# trill-hex.net
KiCad netlist of a schematic drawn in EAGLE
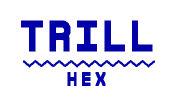
[diagram p0: schematic, sheet 1, part 1 of 2]
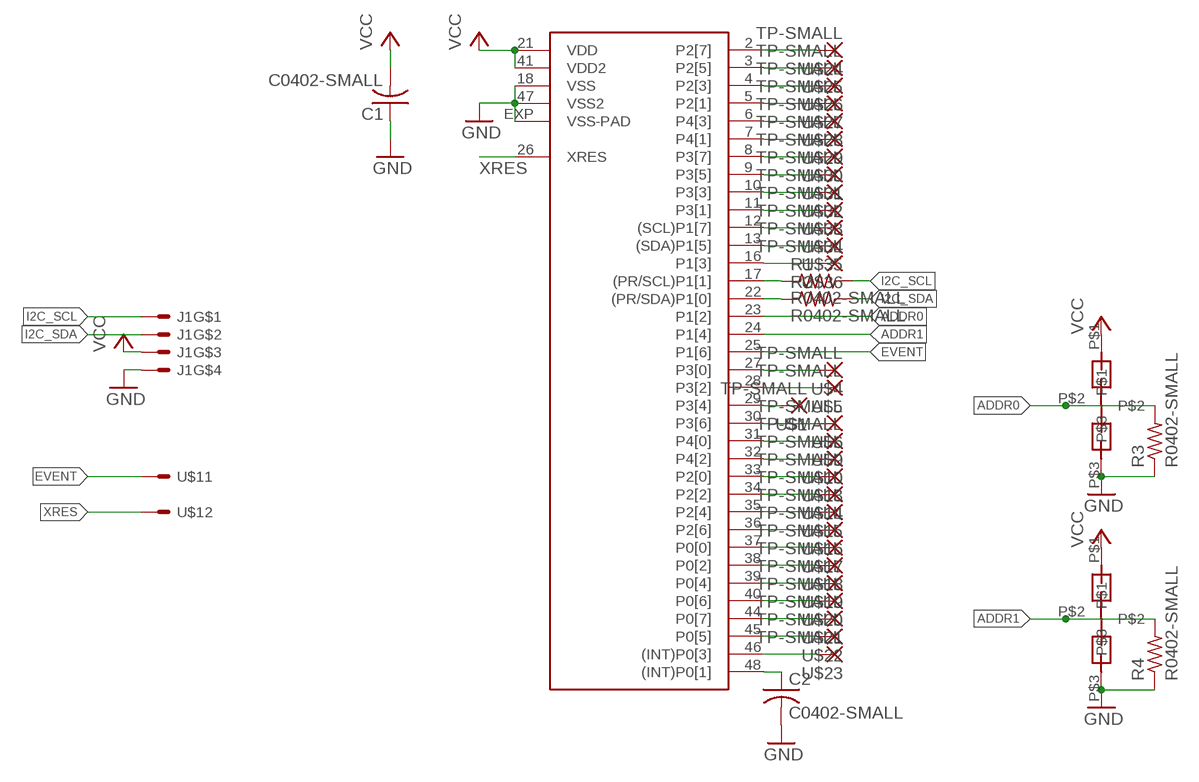
[diagram p1: schematic, sheet 1, part 2 of 2]

(export (version "E")
  (design (tool "Eeschema 10.0.6"))
  (components
    (comp (ref "C1")
      (value "C0402-SMALL")
      (footprint "eagle-import:C0402-SMALL")
      (libsource (lib "eagle-import") (part "C0402-SMALL"))
    )
    (comp (ref "C2")
      (value "C0402-SMALL")
      (footprint "eagle-import:C0402-SMALL")
      (libsource (lib "eagle-import") (part "C0402-SMALL"))
    )
    (comp (ref "IC1")
      (value "CY8C206X6A")
      (footprint "eagle-import:QFN48-LEADS")
      (libsource (lib "eagle-import") (part "CY8C206X6A"))
    )
    (comp (ref "J1")
      (value "GROVE-SMT")
      (footprint "eagle-import:JST-PH-4-SMT")
      (libsource (lib "eagle-import") (part "GROVE-SMT"))
    )
    (comp (ref "R1")
      (value "R0402-SMALL")
      (footprint "eagle-import:C0402-SMALL")
      (libsource (lib "eagle-import") (part "R0402-SMALL"))
    )
    (comp (ref "R2")
      (value "R0402-SMALL")
      (footprint "eagle-import:C0402-SMALL")
      (libsource (lib "eagle-import") (part "R0402-SMALL"))
    )
    (comp (ref "R3")
      (value "R0402-SMALL")
      (footprint "eagle-import:C0402-SMALL")
      (libsource (lib "eagle-import") (part "R0402-SMALL"))
    )
    (comp (ref "R4")
      (value "R0402-SMALL")
      (footprint "eagle-import:C0402-SMALL")
      (libsource (lib "eagle-import") (part "R0402-SMALL"))
    )
    (comp (ref "U$1")
      (value "TP-SMALL")
      (footprint "eagle-import:TESTPAD-SMALL")
      (libsource (lib "eagle-import") (part "TP-SMALL"))
    )
    (comp (ref "U$4")
      (value "TP-SMALL")
      (footprint "eagle-import:TESTPAD-SMALL")
      (libsource (lib "eagle-import") (part "TP-SMALL"))
    )
    (comp (ref "U$5")
      (value "TP-SMALL")
      (footprint "eagle-import:TESTPAD-SMALL")
      (libsource (lib "eagle-import") (part "TP-SMALL"))
    )
    (comp (ref "U$6")
      (value "TP-SMALL")
      (footprint "eagle-import:TESTPAD-SMALL")
      (libsource (lib "eagle-import") (part "TP-SMALL"))
    )
    (comp (ref "U$7")
      (value "SOLDER_JUMPER_3PAD")
      (footprint "eagle-import:SOLDER_JUMPER_3PAD")
      (libsource (lib "eagle-import") (part "SOLDER_JUMPER_3PAD"))
    )
    (comp (ref "U$8")
      (value "SOLDER_JUMPER_3PAD")
      (footprint "eagle-import:SOLDER_JUMPER_3PAD")
      (libsource (lib "eagle-import") (part "SOLDER_JUMPER_3PAD"))
    )
    (comp (ref "U$9")
      (value "TP-SMALL")
      (footprint "eagle-import:TESTPAD-SMALL")
      (libsource (lib "eagle-import") (part "TP-SMALL"))
    )
    (comp (ref "U$10")
      (value "TP-SMALL")
      (footprint "eagle-import:TESTPAD-SMALL")
      (libsource (lib "eagle-import") (part "TP-SMALL"))
    )
    (comp (ref "U$11")
      (value "JST-SMT-EXTRAPAD")
      (footprint "eagle-import:JST-SMT-EXTRAPAD")
      (libsource (lib "eagle-import") (part "JST-SMT-EXTRAPAD"))
    )
    (comp (ref "U$12")
      (value "JST-SMT-EXTRAPAD")
      (footprint "eagle-import:JST-SMT-EXTRAPAD")
      (libsource (lib "eagle-import") (part "JST-SMT-EXTRAPAD"))
    )
    (comp (ref "U$13")
      (value "TP-SMALL")
      (footprint "eagle-import:TESTPAD-SMALL")
      (libsource (lib "eagle-import") (part "TP-SMALL"))
    )
    (comp (ref "U$14")
      (value "TP-SMALL")
      (footprint "eagle-import:TESTPAD-SMALL")
      (libsource (lib "eagle-import") (part "TP-SMALL"))
    )
    (comp (ref "U$15")
      (value "TP-SMALL")
      (footprint "eagle-import:TESTPAD-SMALL")
      (libsource (lib "eagle-import") (part "TP-SMALL"))
    )
    (comp (ref "U$16")
      (value "TP-SMALL")
      (footprint "eagle-import:TESTPAD-SMALL")
      (libsource (lib "eagle-import") (part "TP-SMALL"))
    )
    (comp (ref "U$17")
      (value "TP-SMALL")
      (footprint "eagle-import:TESTPAD-SMALL")
      (libsource (lib "eagle-import") (part "TP-SMALL"))
    )
    (comp (ref "U$18")
      (value "TP-SMALL")
      (footprint "eagle-import:TESTPAD-SMALL")
      (libsource (lib "eagle-import") (part "TP-SMALL"))
    )
    (comp (ref "U$19")
      (value "TP-SMALL")
      (footprint "eagle-import:TESTPAD-SMALL")
      (libsource (lib "eagle-import") (part "TP-SMALL"))
    )
    (comp (ref "U$20")
      (value "TP-SMALL")
      (footprint "eagle-import:TESTPAD-SMALL")
      (libsource (lib "eagle-import") (part "TP-SMALL"))
    )
    (comp (ref "U$21")
      (value "TP-SMALL")
      (footprint "eagle-import:TESTPAD-SMALL")
      (libsource (lib "eagle-import") (part "TP-SMALL"))
    )
    (comp (ref "U$22")
      (value "TP-SMALL")
      (footprint "eagle-import:TESTPAD-SMALL")
      (libsource (lib "eagle-import") (part "TP-SMALL"))
    )
    (comp (ref "U$23")
      (value "TP-SMALL")
      (footprint "eagle-import:TESTPAD-SMALL")
      (libsource (lib "eagle-import") (part "TP-SMALL"))
    )
    (comp (ref "U$24")
      (value "TP-SMALL")
      (footprint "eagle-import:TESTPAD-SMALL")
      (libsource (lib "eagle-import") (part "TP-SMALL"))
    )
    (comp (ref "U$25")
      (value "TP-SMALL")
      (footprint "eagle-import:TESTPAD-SMALL")
      (libsource (lib "eagle-import") (part "TP-SMALL"))
    )
    (comp (ref "U$26")
      (value "TP-SMALL")
      (footprint "eagle-import:TESTPAD-SMALL")
      (libsource (lib "eagle-import") (part "TP-SMALL"))
    )
    (comp (ref "U$27")
      (value "TP-SMALL")
      (footprint "eagle-import:TESTPAD-SMALL")
      (libsource (lib "eagle-import") (part "TP-SMALL"))
    )
    (comp (ref "U$28")
      (value "TP-SMALL")
      (footprint "eagle-import:TESTPAD-SMALL")
      (libsource (lib "eagle-import") (part "TP-SMALL"))
    )
    (comp (ref "U$29")
      (value "TP-SMALL")
      (footprint "eagle-import:TESTPAD-SMALL")
      (libsource (lib "eagle-import") (part "TP-SMALL"))
    )
    (comp (ref "U$30")
      (value "TP-SMALL")
      (footprint "eagle-import:TESTPAD-SMALL")
      (libsource (lib "eagle-import") (part "TP-SMALL"))
    )
    (comp (ref "U$31")
      (value "TP-SMALL")
      (footprint "eagle-import:TESTPAD-SMALL")
      (libsource (lib "eagle-import") (part "TP-SMALL"))
    )
    (comp (ref "U$32")
      (value "TP-SMALL")
      (footprint "eagle-import:TESTPAD-SMALL")
      (libsource (lib "eagle-import") (part "TP-SMALL"))
    )
    (comp (ref "U$33")
      (value "TP-SMALL")
      (footprint "eagle-import:TESTPAD-SMALL")
      (libsource (lib "eagle-import") (part "TP-SMALL"))
    )
    (comp (ref "U$34")
      (value "TP-SMALL")
      (footprint "eagle-import:TESTPAD-SMALL")
      (libsource (lib "eagle-import") (part "TP-SMALL"))
    )
    (comp (ref "U$35")
      (value "TP-SMALL")
      (footprint "eagle-import:TESTPAD-SMALL")
      (libsource (lib "eagle-import") (part "TP-SMALL"))
    )
    (comp (ref "U$36")
      (value "TP-SMALL")
      (footprint "eagle-import:TESTPAD-SMALL")
      (libsource (lib "eagle-import") (part "TP-SMALL"))
    )
  )
  (nets
    (net (code "1") (name "ADDR0") (class "Default")
      (node (ref "IC1") (pin "23") (pinfunction "P1[2]_23") (pintype "bidirectional"))
      (node (ref "R3") (pin "P$2") (pinfunction "2_P$2") (pintype "passive"))
      (node (ref "U$7") (pin "P$2") (pinfunction "P$2_P$2") (pintype "bidirectional"))
    )
    (net (code "2") (name "ADDR1") (class "Default")
      (node (ref "IC1") (pin "24") (pinfunction "P1[4]_24") (pintype "bidirectional"))
      (node (ref "R4") (pin "P$2") (pinfunction "2_P$2") (pintype "passive"))
      (node (ref "U$8") (pin "P$2") (pinfunction "P$2_P$2") (pintype "bidirectional"))
    )
    (net (code "3") (name "EVENT") (class "Default")
      (node (ref "IC1") (pin "25") (pinfunction "P1[6]_25") (pintype "bidirectional"))
      (node (ref "U$11") (pin "P$1") (pinfunction "S_P$1") (pintype "passive"))
    )
    (net (code "4") (name "GND") (class "Default")
      (node (ref "C1") (pin "P$1") (pinfunction "1_P$1") (pintype "passive"))
      (node (ref "C2") (pin "P$2") (pinfunction "2_P$2") (pintype "passive"))
      (node (ref "IC1") (pin "18") (pinfunction "VSS_18") (pintype "bidirectional"))
      (node (ref "IC1") (pin "47") (pinfunction "VSS2_47") (pintype "bidirectional"))
      (node (ref "IC1") (pin "EXP") (pinfunction "VSS-PAD_EXP") (pintype "bidirectional"))
      (node (ref "J1") (pin "4") (pinfunction "S_4") (pintype "passive"))
      (node (ref "R3") (pin "P$1") (pinfunction "1_P$1") (pintype "passive"))
      (node (ref "R4") (pin "P$1") (pinfunction "1_P$1") (pintype "passive"))
      (node (ref "U$7") (pin "P$3") (pinfunction "P$3_P$3") (pintype "bidirectional"))
      (node (ref "U$8") (pin "P$3") (pinfunction "P$3_P$3") (pintype "bidirectional"))
    )
    (net (code "5") (name "I2C_SCL") (class "Default")
      (node (ref "J1") (pin "1") (pinfunction "S_1") (pintype "passive"))
      (node (ref "R1") (pin "P$2") (pinfunction "2_P$2") (pintype "passive"))
    )
    (net (code "6") (name "I2C_SDA") (class "Default")
      (node (ref "J1") (pin "2") (pinfunction "S_2") (pintype "passive"))
      (node (ref "R2") (pin "P$2") (pinfunction "2_P$2") (pintype "passive"))
    )
    (net (code "7") (name "Net-(C2-1)") (class "Default")
      (node (ref "C2") (pin "P$1") (pinfunction "1_P$1") (pintype "passive"))
      (node (ref "IC1") (pin "48") (pinfunction "(INT)P0[1]_48") (pintype "bidirectional"))
    )
    (net (code "8") (name "Net-(IC1-(INT)P0[3])") (class "Default")
      (node (ref "IC1") (pin "46") (pinfunction "(INT)P0[3]_46") (pintype "bidirectional"))
      (node (ref "U$23") (pin "P$1") (pinfunction "P_P$1") (pintype "passive"))
    )
    (net (code "9") (name "Net-(IC1-(PR{slash}SCL)P1[1])") (class "Default")
      (node (ref "IC1") (pin "17") (pinfunction "(PR/SCL)P1[1]_17") (pintype "bidirectional"))
      (node (ref "R1") (pin "P$1") (pinfunction "1_P$1") (pintype "passive"))
    )
    (net (code "10") (name "Net-(IC1-(PR{slash}SDA)P1[0])") (class "Default")
      (node (ref "IC1") (pin "22") (pinfunction "(PR/SDA)P1[0]_22") (pintype "bidirectional"))
      (node (ref "R2") (pin "P$1") (pinfunction "1_P$1") (pintype "passive"))
    )
    (net (code "11") (name "Net-(IC1-(SCL)P1[7])") (class "Default")
      (node (ref "IC1") (pin "12") (pinfunction "(SCL)P1[7]_12") (pintype "bidirectional"))
      (node (ref "U$34") (pin "P$1") (pinfunction "P_P$1") (pintype "passive"))
    )
    (net (code "12") (name "Net-(IC1-(SDA)P1[5])") (class "Default")
      (node (ref "IC1") (pin "13") (pinfunction "(SDA)P1[5]_13") (pintype "bidirectional"))
      (node (ref "U$35") (pin "P$1") (pinfunction "P_P$1") (pintype "passive"))
    )
    (net (code "13") (name "Net-(IC1-P0[0])") (class "Default")
      (node (ref "IC1") (pin "37") (pinfunction "P0[0]_37") (pintype "bidirectional"))
      (node (ref "U$17") (pin "P$1") (pinfunction "P_P$1") (pintype "passive"))
    )
    (net (code "14") (name "Net-(IC1-P0[2])") (class "Default")
      (node (ref "IC1") (pin "38") (pinfunction "P0[2]_38") (pintype "bidirectional"))
      (node (ref "U$18") (pin "P$1") (pinfunction "P_P$1") (pintype "passive"))
    )
    (net (code "15") (name "Net-(IC1-P0[4])") (class "Default")
      (node (ref "IC1") (pin "39") (pinfunction "P0[4]_39") (pintype "bidirectional"))
      (node (ref "U$19") (pin "P$1") (pinfunction "P_P$1") (pintype "passive"))
    )
    (net (code "16") (name "Net-(IC1-P0[5])") (class "Default")
      (node (ref "IC1") (pin "45") (pinfunction "P0[5]_45") (pintype "bidirectional"))
      (node (ref "U$22") (pin "P$1") (pinfunction "P_P$1") (pintype "passive"))
    )
    (net (code "17") (name "Net-(IC1-P0[6])") (class "Default")
      (node (ref "IC1") (pin "40") (pinfunction "P0[6]_40") (pintype "bidirectional"))
      (node (ref "U$20") (pin "P$1") (pinfunction "P_P$1") (pintype "passive"))
    )
    (net (code "18") (name "Net-(IC1-P0[7])") (class "Default")
      (node (ref "IC1") (pin "44") (pinfunction "P0[7]_44") (pintype "bidirectional"))
      (node (ref "U$21") (pin "P$1") (pinfunction "P_P$1") (pintype "passive"))
    )
    (net (code "19") (name "Net-(IC1-P1[3])") (class "Default")
      (node (ref "IC1") (pin "16") (pinfunction "P1[3]_16") (pintype "bidirectional"))
      (node (ref "U$36") (pin "P$1") (pinfunction "P_P$1") (pintype "passive"))
    )
    (net (code "20") (name "Net-(IC1-P2[0])") (class "Default")
      (node (ref "IC1") (pin "33") (pinfunction "P2[0]_33") (pintype "bidirectional"))
      (node (ref "U$13") (pin "P$1") (pinfunction "P_P$1") (pintype "passive"))
    )
    (net (code "21") (name "Net-(IC1-P2[1])") (class "Default")
      (node (ref "IC1") (pin "5") (pinfunction "P2[1]_5") (pintype "bidirectional"))
      (node (ref "U$27") (pin "P$1") (pinfunction "P_P$1") (pintype "passive"))
    )
    (net (code "22") (name "Net-(IC1-P2[2])") (class "Default")
      (node (ref "IC1") (pin "34") (pinfunction "P2[2]_34") (pintype "bidirectional"))
      (node (ref "U$14") (pin "P$1") (pinfunction "P_P$1") (pintype "passive"))
    )
    (net (code "23") (name "Net-(IC1-P2[3])") (class "Default")
      (node (ref "IC1") (pin "4") (pinfunction "P2[3]_4") (pintype "bidirectional"))
      (node (ref "U$26") (pin "P$1") (pinfunction "P_P$1") (pintype "passive"))
    )
    (net (code "24") (name "Net-(IC1-P2[4])") (class "Default")
      (node (ref "IC1") (pin "35") (pinfunction "P2[4]_35") (pintype "bidirectional"))
      (node (ref "U$15") (pin "P$1") (pinfunction "P_P$1") (pintype "passive"))
    )
    (net (code "25") (name "Net-(IC1-P2[5])") (class "Default")
      (node (ref "IC1") (pin "3") (pinfunction "P2[5]_3") (pintype "bidirectional"))
      (node (ref "U$25") (pin "P$1") (pinfunction "P_P$1") (pintype "passive"))
    )
    (net (code "26") (name "Net-(IC1-P2[6])") (class "Default")
      (node (ref "IC1") (pin "36") (pinfunction "P2[6]_36") (pintype "bidirectional"))
      (node (ref "U$16") (pin "P$1") (pinfunction "P_P$1") (pintype "passive"))
    )
    (net (code "27") (name "Net-(IC1-P2[7])") (class "Default")
      (node (ref "IC1") (pin "2") (pinfunction "P2[7]_2") (pintype "bidirectional"))
      (node (ref "U$24") (pin "P$1") (pinfunction "P_P$1") (pintype "passive"))
    )
    (net (code "28") (name "Net-(IC1-P3[0])") (class "Default")
      (node (ref "IC1") (pin "27") (pinfunction "P3[0]_27") (pintype "bidirectional"))
      (node (ref "U$4") (pin "P$1") (pinfunction "P_P$1") (pintype "passive"))
    )
    (net (code "29") (name "Net-(IC1-P3[1])") (class "Default")
      (node (ref "IC1") (pin "11") (pinfunction "P3[1]_11") (pintype "bidirectional"))
      (node (ref "U$33") (pin "P$1") (pinfunction "P_P$1") (pintype "passive"))
    )
    (net (code "30") (name "Net-(IC1-P3[2])") (class "Default")
      (node (ref "IC1") (pin "28") (pinfunction "P3[2]_28") (pintype "bidirectional"))
      (node (ref "U$5") (pin "P$1") (pinfunction "P_P$1") (pintype "passive"))
    )
    (net (code "31") (name "Net-(IC1-P3[3])") (class "Default")
      (node (ref "IC1") (pin "10") (pinfunction "P3[3]_10") (pintype "bidirectional"))
      (node (ref "U$32") (pin "P$1") (pinfunction "P_P$1") (pintype "passive"))
    )
    (net (code "32") (name "Net-(IC1-P3[4])") (class "Default")
      (node (ref "IC1") (pin "29") (pinfunction "P3[4]_29") (pintype "bidirectional"))
      (node (ref "U$1") (pin "P$1") (pinfunction "P_P$1") (pintype "passive"))
    )
    (net (code "33") (name "Net-(IC1-P3[5])") (class "Default")
      (node (ref "IC1") (pin "9") (pinfunction "P3[5]_9") (pintype "bidirectional"))
      (node (ref "U$31") (pin "P$1") (pinfunction "P_P$1") (pintype "passive"))
    )
    (net (code "34") (name "Net-(IC1-P3[6])") (class "Default")
      (node (ref "IC1") (pin "30") (pinfunction "P3[6]_30") (pintype "bidirectional"))
      (node (ref "U$6") (pin "P$1") (pinfunction "P_P$1") (pintype "passive"))
    )
    (net (code "35") (name "Net-(IC1-P3[7])") (class "Default")
      (node (ref "IC1") (pin "8") (pinfunction "P3[7]_8") (pintype "bidirectional"))
      (node (ref "U$30") (pin "P$1") (pinfunction "P_P$1") (pintype "passive"))
    )
    (net (code "36") (name "Net-(IC1-P4[0])") (class "Default")
      (node (ref "IC1") (pin "31") (pinfunction "P4[0]_31") (pintype "bidirectional"))
      (node (ref "U$9") (pin "P$1") (pinfunction "P_P$1") (pintype "passive"))
    )
    (net (code "37") (name "Net-(IC1-P4[1])") (class "Default")
      (node (ref "IC1") (pin "7") (pinfunction "P4[1]_7") (pintype "bidirectional"))
      (node (ref "U$29") (pin "P$1") (pinfunction "P_P$1") (pintype "passive"))
    )
    (net (code "38") (name "Net-(IC1-P4[2])") (class "Default")
      (node (ref "IC1") (pin "32") (pinfunction "P4[2]_32") (pintype "bidirectional"))
      (node (ref "U$10") (pin "P$1") (pinfunction "P_P$1") (pintype "passive"))
    )
    (net (code "39") (name "Net-(IC1-P4[3])") (class "Default")
      (node (ref "IC1") (pin "6") (pinfunction "P4[3]_6") (pintype "bidirectional"))
      (node (ref "U$28") (pin "P$1") (pinfunction "P_P$1") (pintype "passive"))
    )
    (net (code "40") (name "VCC") (class "Default")
      (node (ref "C1") (pin "P$2") (pinfunction "2_P$2") (pintype "passive"))
      (node (ref "IC1") (pin "21") (pinfunction "VDD_21") (pintype "bidirectional"))
      (node (ref "IC1") (pin "41") (pinfunction "VDD2_41") (pintype "bidirectional"))
      (node (ref "J1") (pin "3") (pinfunction "S_3") (pintype "passive"))
      (node (ref "U$7") (pin "P$1") (pinfunction "P$1_P$1") (pintype "bidirectional"))
      (node (ref "U$8") (pin "P$1") (pinfunction "P$1_P$1") (pintype "bidirectional"))
    )
    (net (code "41") (name "XRES") (class "Default")
      (node (ref "IC1") (pin "26") (pinfunction "XRES_26") (pintype "bidirectional"))
      (node (ref "U$12") (pin "P$1") (pinfunction "S_P$1") (pintype "passive"))
    )
  )
)
